# LIDO-HW_100_InputStage_1.net
KiCad netlist of a schematic drawn in Altium Designer
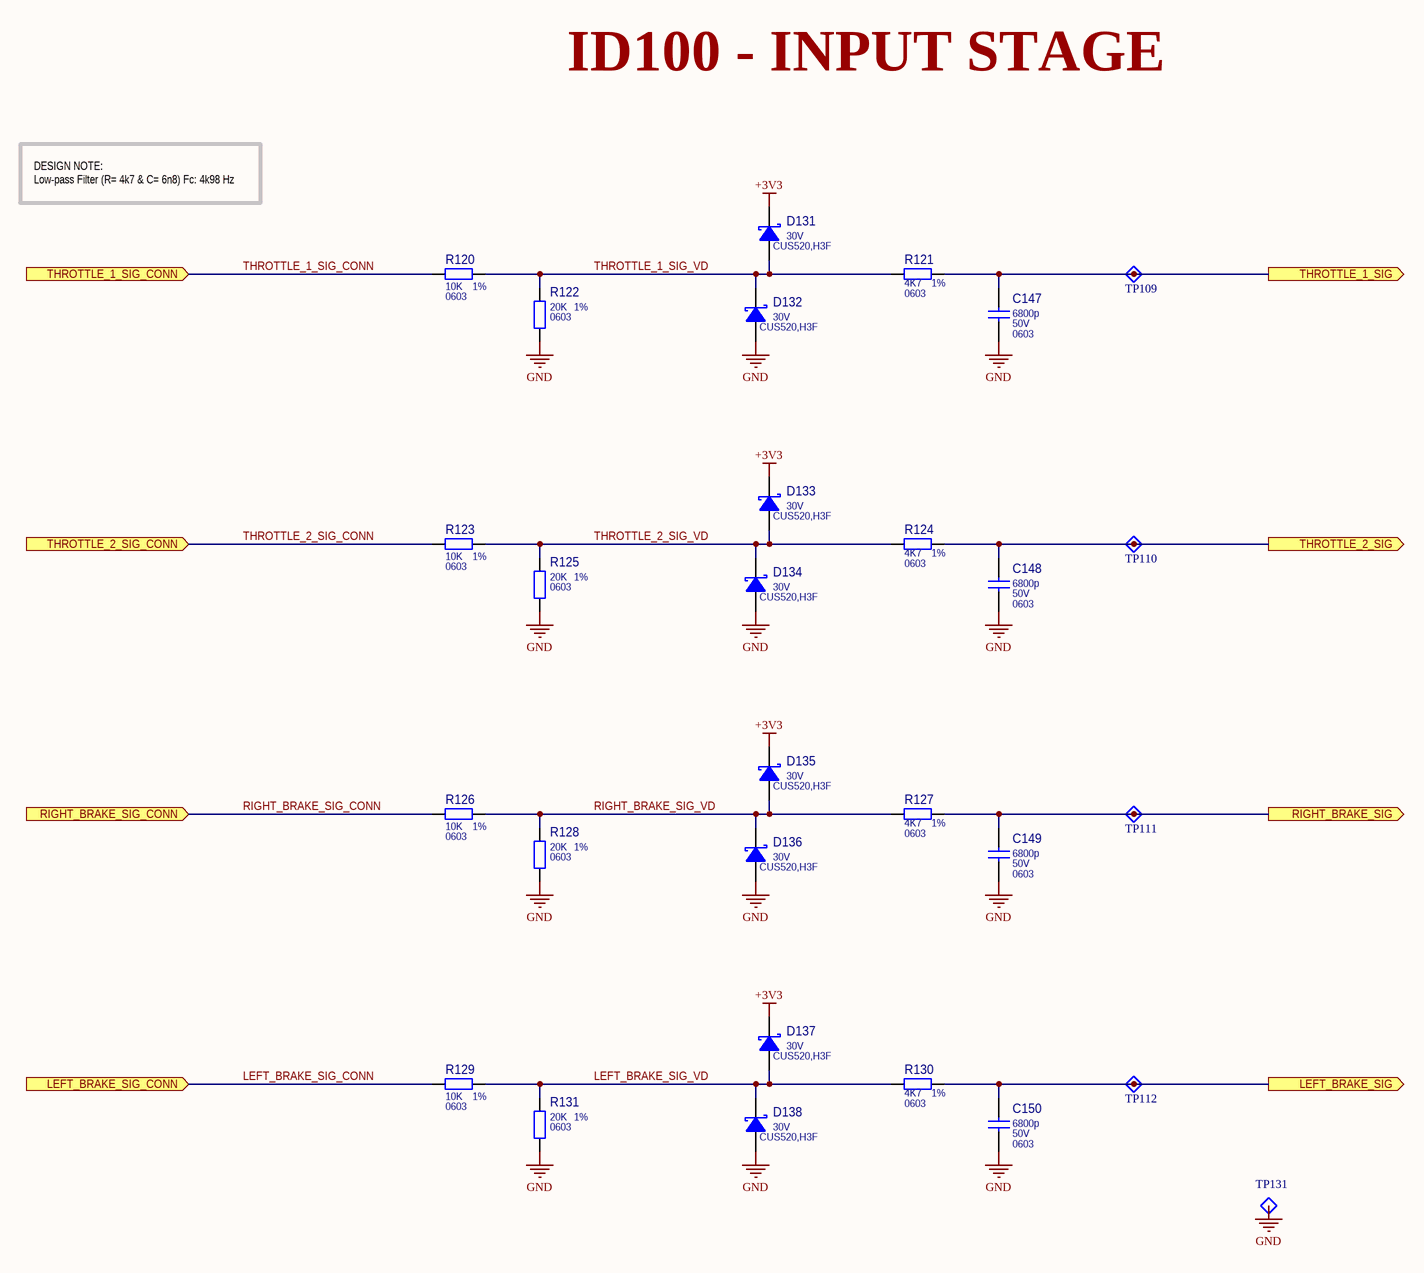
[diagram p0: LIDO-HW.100.InputStage_1.SchDoc]

(export (version "E")
  (design (tool "Eeschema 10.0.6"))
  (components
    (comp (ref "C147")
      (value "6800p")
      (footprint "CAP_0603_1608X90-N_MURATA_A")
      (description "CAP CER 6800PF 50V X7R 0603")
      (fields
        (field (name "MANUFACTURER PART NUMBER") "CGA3E2X7R1H682K080AA")
        (field (name "MANUFACTURER") "TDK Corporation")
        (field (name "PART VALUE 2") "50V")
        (field (name "PART PACKAGE") "0603")
      )
      (libsource (lib "DB_Library") (part "Ceramic"))
    )
    (comp (ref "C148")
      (value "6800p")
      (footprint "CAP_0603_1608X90-N_MURATA_A")
      (description "CAP CER 6800PF 50V X7R 0603")
      (fields
        (field (name "MANUFACTURER PART NUMBER") "CGA3E2X7R1H682K080AA")
        (field (name "MANUFACTURER") "TDK Corporation")
        (field (name "PART VALUE 2") "50V")
        (field (name "PART PACKAGE") "0603")
      )
      (libsource (lib "DB_Library") (part "Ceramic"))
    )
    (comp (ref "C149")
      (value "6800p")
      (footprint "CAP_0603_1608X90-N_MURATA_A")
      (description "CAP CER 6800PF 50V X7R 0603")
      (fields
        (field (name "MANUFACTURER PART NUMBER") "CGA3E2X7R1H682K080AA")
        (field (name "MANUFACTURER") "TDK Corporation")
        (field (name "PART VALUE 2") "50V")
        (field (name "PART PACKAGE") "0603")
      )
      (libsource (lib "DB_Library") (part "Ceramic"))
    )
    (comp (ref "C150")
      (value "6800p")
      (footprint "CAP_0603_1608X90-N_MURATA_A")
      (description "CAP CER 6800PF 50V X7R 0603")
      (fields
        (field (name "MANUFACTURER PART NUMBER") "CGA3E2X7R1H682K080AA")
        (field (name "MANUFACTURER") "TDK Corporation")
        (field (name "PART VALUE 2") "50V")
        (field (name "PART PACKAGE") "0603")
      )
      (libsource (lib "DB_Library") (part "Ceramic"))
    )
    (comp (ref "D131")
      (value "30V")
      (footprint "NXP_SOD-323_250X125X95L30x32_A")
      (description "DIODE SCHOTTKY 30V 200MA")
      (fields
        (field (name "MANUFACTURER PART NUMBER") "CUS520,H3F")
        (field (name "MANUFACTURER") "Toshiba Semiconductor and Storage")
        (field (name "OBSOLETE PART") "False")
      )
      (libsource (lib "DB_Library") (part "Schottky_A"))
    )
    (comp (ref "D132")
      (value "30V")
      (footprint "NXP_SOD-323_250X125X95L30x32_A")
      (description "DIODE SCHOTTKY 30V 200MA")
      (fields
        (field (name "MANUFACTURER PART NUMBER") "CUS520,H3F")
        (field (name "MANUFACTURER") "Toshiba Semiconductor and Storage")
        (field (name "OBSOLETE PART") "False")
      )
      (libsource (lib "DB_Library") (part "Schottky_A"))
    )
    (comp (ref "D133")
      (value "30V")
      (footprint "NXP_SOD-323_250X125X95L30x32_A")
      (description "DIODE SCHOTTKY 30V 200MA")
      (fields
        (field (name "MANUFACTURER PART NUMBER") "CUS520,H3F")
        (field (name "MANUFACTURER") "Toshiba Semiconductor and Storage")
        (field (name "OBSOLETE PART") "False")
      )
      (libsource (lib "DB_Library") (part "Schottky_A"))
    )
    (comp (ref "D134")
      (value "30V")
      (footprint "NXP_SOD-323_250X125X95L30x32_A")
      (description "DIODE SCHOTTKY 30V 200MA")
      (fields
        (field (name "MANUFACTURER PART NUMBER") "CUS520,H3F")
        (field (name "MANUFACTURER") "Toshiba Semiconductor and Storage")
        (field (name "OBSOLETE PART") "False")
      )
      (libsource (lib "DB_Library") (part "Schottky_A"))
    )
    (comp (ref "D135")
      (value "30V")
      (footprint "NXP_SOD-323_250X125X95L30x32_A")
      (description "DIODE SCHOTTKY 30V 200MA")
      (fields
        (field (name "MANUFACTURER PART NUMBER") "CUS520,H3F")
        (field (name "MANUFACTURER") "Toshiba Semiconductor and Storage")
        (field (name "OBSOLETE PART") "False")
      )
      (libsource (lib "DB_Library") (part "Schottky_A"))
    )
    (comp (ref "D136")
      (value "30V")
      (footprint "NXP_SOD-323_250X125X95L30x32_A")
      (description "DIODE SCHOTTKY 30V 200MA")
      (fields
        (field (name "MANUFACTURER PART NUMBER") "CUS520,H3F")
        (field (name "MANUFACTURER") "Toshiba Semiconductor and Storage")
        (field (name "OBSOLETE PART") "False")
      )
      (libsource (lib "DB_Library") (part "Schottky_A"))
    )
    (comp (ref "D137")
      (value "30V")
      (footprint "NXP_SOD-323_250X125X95L30x32_A")
      (description "DIODE SCHOTTKY 30V 200MA")
      (fields
        (field (name "MANUFACTURER PART NUMBER") "CUS520,H3F")
        (field (name "MANUFACTURER") "Toshiba Semiconductor and Storage")
        (field (name "OBSOLETE PART") "False")
      )
      (libsource (lib "DB_Library") (part "Schottky_A"))
    )
    (comp (ref "D138")
      (value "30V")
      (footprint "NXP_SOD-323_250X125X95L30x32_A")
      (description "DIODE SCHOTTKY 30V 200MA")
      (fields
        (field (name "MANUFACTURER PART NUMBER") "CUS520,H3F")
        (field (name "MANUFACTURER") "Toshiba Semiconductor and Storage")
        (field (name "OBSOLETE PART") "False")
      )
      (libsource (lib "DB_Library") (part "Schottky_A"))
    )
    (comp (ref "R120")
      (value "10K")
      (footprint "RES_0603_1608X60-N_YAGEO_A")
      (description "RES 10K OHM 1% 1/10W 0603")
      (fields
        (field (name "MANUFACTURER PART NUMBER") "RC0603FR-0710KL")
        (field (name "MANUFACTURER") "YAGEO")
        (field (name "PART VALUE 2") "1%")
        (field (name "PART PACKAGE") "0603")
      )
      (libsource (lib "DB_Library") (part "Resistor"))
    )
    (comp (ref "R121")
      (value "4K7")
      (footprint "RES_0603_1608X60-N_YAGEO_A")
      (description "RES SMD 4.7K OHM 1% 1/10W 0603")
      (fields
        (field (name "MANUFACTURER PART NUMBER") "ERJ-3EKF4701V")
        (field (name "MANUFACTURER") "Panasonic Electronic Components")
        (field (name "PART VALUE 2") "1%")
        (field (name "PART PACKAGE") "0603")
      )
      (libsource (lib "") (part "Resistor_1"))
    )
    (comp (ref "R122")
      (value "20K")
      (footprint "RES_0603_1608X60-N_YAGEO_A")
      (description "RES SMD 20K OHM 1% 1/10W 0603")
      (fields
        (field (name "MANUFACTURER PART NUMBER") "ERJ-3EKF2002V")
        (field (name "MANUFACTURER") "Panasonic Electronic Components")
        (field (name "PART VALUE 2") "1%")
        (field (name "PART PACKAGE") "0603")
      )
      (libsource (lib "") (part "Resistor_2"))
    )
    (comp (ref "R123")
      (value "10K")
      (footprint "RES_0603_1608X60-N_YAGEO_A")
      (description "RES 10K OHM 1% 1/10W 0603")
      (fields
        (field (name "MANUFACTURER PART NUMBER") "RC0603FR-0710KL")
        (field (name "MANUFACTURER") "YAGEO")
        (field (name "PART VALUE 2") "1%")
        (field (name "PART PACKAGE") "0603")
      )
      (libsource (lib "DB_Library") (part "Resistor"))
    )
    (comp (ref "R124")
      (value "4K7")
      (footprint "RES_0603_1608X60-N_YAGEO_A")
      (description "RES SMD 4.7K OHM 1% 1/10W 0603")
      (fields
        (field (name "MANUFACTURER PART NUMBER") "ERJ-3EKF4701V")
        (field (name "MANUFACTURER") "Panasonic Electronic Components")
        (field (name "PART VALUE 2") "1%")
        (field (name "PART PACKAGE") "0603")
      )
      (libsource (lib "") (part "Resistor_1"))
    )
    (comp (ref "R125")
      (value "20K")
      (footprint "RES_0603_1608X60-N_YAGEO_A")
      (description "RES SMD 20K OHM 1% 1/10W 0603")
      (fields
        (field (name "MANUFACTURER PART NUMBER") "ERJ-3EKF2002V")
        (field (name "MANUFACTURER") "Panasonic Electronic Components")
        (field (name "PART VALUE 2") "1%")
        (field (name "PART PACKAGE") "0603")
      )
      (libsource (lib "") (part "Resistor_2"))
    )
    (comp (ref "R126")
      (value "10K")
      (footprint "RES_0603_1608X60-N_YAGEO_A")
      (description "RES 10K OHM 1% 1/10W 0603")
      (fields
        (field (name "MANUFACTURER PART NUMBER") "RC0603FR-0710KL")
        (field (name "MANUFACTURER") "YAGEO")
        (field (name "PART VALUE 2") "1%")
        (field (name "PART PACKAGE") "0603")
      )
      (libsource (lib "DB_Library") (part "Resistor"))
    )
    (comp (ref "R127")
      (value "4K7")
      (footprint "RES_0603_1608X60-N_YAGEO_A")
      (description "RES SMD 4.7K OHM 1% 1/10W 0603")
      (fields
        (field (name "MANUFACTURER PART NUMBER") "ERJ-3EKF4701V")
        (field (name "MANUFACTURER") "Panasonic Electronic Components")
        (field (name "PART VALUE 2") "1%")
        (field (name "PART PACKAGE") "0603")
      )
      (libsource (lib "") (part "Resistor_1"))
    )
    (comp (ref "R128")
      (value "20K")
      (footprint "RES_0603_1608X60-N_YAGEO_A")
      (description "RES SMD 20K OHM 1% 1/10W 0603")
      (fields
        (field (name "MANUFACTURER PART NUMBER") "ERJ-3EKF2002V")
        (field (name "MANUFACTURER") "Panasonic Electronic Components")
        (field (name "PART VALUE 2") "1%")
        (field (name "PART PACKAGE") "0603")
      )
      (libsource (lib "") (part "Resistor_2"))
    )
    (comp (ref "R129")
      (value "10K")
      (footprint "RES_0603_1608X60-N_YAGEO_A")
      (description "RES 10K OHM 1% 1/10W 0603")
      (fields
        (field (name "MANUFACTURER PART NUMBER") "RC0603FR-0710KL")
        (field (name "MANUFACTURER") "YAGEO")
        (field (name "PART VALUE 2") "1%")
        (field (name "PART PACKAGE") "0603")
      )
      (libsource (lib "DB_Library") (part "Resistor"))
    )
    (comp (ref "R130")
      (value "4K7")
      (footprint "RES_0603_1608X60-N_YAGEO_A")
      (description "RES SMD 4.7K OHM 1% 1/10W 0603")
      (fields
        (field (name "MANUFACTURER PART NUMBER") "ERJ-3EKF4701V")
        (field (name "MANUFACTURER") "Panasonic Electronic Components")
        (field (name "PART VALUE 2") "1%")
        (field (name "PART PACKAGE") "0603")
      )
      (libsource (lib "") (part "Resistor_1"))
    )
    (comp (ref "R131")
      (value "20K")
      (footprint "RES_0603_1608X60-N_YAGEO_A")
      (description "RES SMD 20K OHM 1% 1/10W 0603")
      (fields
        (field (name "MANUFACTURER PART NUMBER") "ERJ-3EKF2002V")
        (field (name "MANUFACTURER") "Panasonic Electronic Components")
        (field (name "PART VALUE 2") "1%")
        (field (name "PART PACKAGE") "0603")
      )
      (libsource (lib "") (part "Resistor_2"))
    )
    (comp (ref "TP109")
      (value "TestPoint_A")
      (footprint "TESTPOINT_1D_A")
      (description "Pad Diamater 1mm")
      (fields (field (name "PART") "Test Point 1D A") (field (name "OBSOLETE PART") "False"))
      (libsource (lib "DB_Library") (part "TestPoint_A"))
    )
    (comp (ref "TP110")
      (value "TestPoint_A")
      (footprint "TESTPOINT_1D_A")
      (description "Pad Diamater 1mm")
      (fields (field (name "PART") "Test Point 1D A") (field (name "OBSOLETE PART") "False"))
      (libsource (lib "DB_Library") (part "TestPoint_A"))
    )
    (comp (ref "TP111")
      (value "TestPoint_A")
      (footprint "TESTPOINT_1D_A")
      (description "Pad Diamater 1mm")
      (fields (field (name "PART") "Test Point 1D A") (field (name "OBSOLETE PART") "False"))
      (libsource (lib "DB_Library") (part "TestPoint_A"))
    )
    (comp (ref "TP112")
      (value "TestPoint_A")
      (footprint "TESTPOINT_1D_A")
      (description "Pad Diamater 1mm")
      (fields (field (name "PART") "Test Point 1D A") (field (name "OBSOLETE PART") "False"))
      (libsource (lib "DB_Library") (part "TestPoint_A"))
    )
    (comp (ref "TP131")
      (value "TestPoint_A")
      (footprint "TESTPOINT_1D_A")
      (description "Pad Diamater 1mm")
      (fields (field (name "PART") "Test Point 1D A") (field (name "OBSOLETE PART") "False"))
      (libsource (lib "DB_Library") (part "TestPoint_A"))
    )
  )
  (nets
    (net (code "1") (name "+3V3") (class "Default")
      (node (ref "D131") (pin "C") (pinfunction "C_C") (pintype "passive"))
      (node (ref "D133") (pin "C") (pinfunction "C_C") (pintype "passive"))
      (node (ref "D135") (pin "C") (pinfunction "C_C") (pintype "passive"))
      (node (ref "D137") (pin "C") (pinfunction "C_C") (pintype "passive"))
    )
    (net (code "2") (name "/LEFT_BRAKE_SIG") (class "Default")
      (node (ref "C150") (pin "1") (pinfunction "1_1") (pintype "passive"))
      (node (ref "R130") (pin "2") (pinfunction "2_2") (pintype "passive"))
      (node (ref "TP112") (pin "1") (pinfunction "TP_1") (pintype "passive"))
    )
    (net (code "3") (name "/LEFT_BRAKE_SIG_CONN") (class "Default")
      (node (ref "R129") (pin "2") (pinfunction "2_2") (pintype "passive"))
    )
    (net (code "4") (name "/LEFT_BRAKE_SIG_VD") (class "Default")
      (node (ref "D137") (pin "A") (pinfunction "A_A") (pintype "passive"))
      (node (ref "D138") (pin "C") (pinfunction "C_C") (pintype "passive"))
      (node (ref "R129") (pin "1") (pinfunction "1_1") (pintype "passive"))
      (node (ref "R130") (pin "1") (pinfunction "1_1") (pintype "passive"))
      (node (ref "R131") (pin "2") (pinfunction "2_2") (pintype "passive"))
    )
    (net (code "5") (name "/RIGHT_BRAKE_SIG") (class "Default")
      (node (ref "C149") (pin "1") (pinfunction "1_1") (pintype "passive"))
      (node (ref "R127") (pin "2") (pinfunction "2_2") (pintype "passive"))
      (node (ref "TP111") (pin "1") (pinfunction "TP_1") (pintype "passive"))
    )
    (net (code "6") (name "/RIGHT_BRAKE_SIG_CONN") (class "Default")
      (node (ref "R126") (pin "2") (pinfunction "2_2") (pintype "passive"))
    )
    (net (code "7") (name "/RIGHT_BRAKE_SIG_VD") (class "Default")
      (node (ref "D135") (pin "A") (pinfunction "A_A") (pintype "passive"))
      (node (ref "D136") (pin "C") (pinfunction "C_C") (pintype "passive"))
      (node (ref "R126") (pin "1") (pinfunction "1_1") (pintype "passive"))
      (node (ref "R127") (pin "1") (pinfunction "1_1") (pintype "passive"))
      (node (ref "R128") (pin "2") (pinfunction "2_2") (pintype "passive"))
    )
    (net (code "8") (name "/THROTTLE_1_SIG") (class "Default")
      (node (ref "C147") (pin "1") (pinfunction "1_1") (pintype "passive"))
      (node (ref "R121") (pin "2") (pinfunction "2_2") (pintype "passive"))
      (node (ref "TP109") (pin "1") (pinfunction "TP_1") (pintype "passive"))
    )
    (net (code "9") (name "/THROTTLE_1_SIG_CONN") (class "Default")
      (node (ref "R120") (pin "2") (pinfunction "2_2") (pintype "passive"))
    )
    (net (code "10") (name "/THROTTLE_1_SIG_VD") (class "Default")
      (node (ref "D131") (pin "A") (pinfunction "A_A") (pintype "passive"))
      (node (ref "D132") (pin "C") (pinfunction "C_C") (pintype "passive"))
      (node (ref "R120") (pin "1") (pinfunction "1_1") (pintype "passive"))
      (node (ref "R121") (pin "1") (pinfunction "1_1") (pintype "passive"))
      (node (ref "R122") (pin "2") (pinfunction "2_2") (pintype "passive"))
    )
    (net (code "11") (name "/THROTTLE_2_SIG") (class "Default")
      (node (ref "C148") (pin "1") (pinfunction "1_1") (pintype "passive"))
      (node (ref "R124") (pin "2") (pinfunction "2_2") (pintype "passive"))
      (node (ref "TP110") (pin "1") (pinfunction "TP_1") (pintype "passive"))
    )
    (net (code "12") (name "/THROTTLE_2_SIG_CONN") (class "Default")
      (node (ref "R123") (pin "2") (pinfunction "2_2") (pintype "passive"))
    )
    (net (code "13") (name "/THROTTLE_2_SIG_VD") (class "Default")
      (node (ref "D133") (pin "A") (pinfunction "A_A") (pintype "passive"))
      (node (ref "D134") (pin "C") (pinfunction "C_C") (pintype "passive"))
      (node (ref "R123") (pin "1") (pinfunction "1_1") (pintype "passive"))
      (node (ref "R124") (pin "1") (pinfunction "1_1") (pintype "passive"))
      (node (ref "R125") (pin "2") (pinfunction "2_2") (pintype "passive"))
    )
    (net (code "14") (name "GND") (class "Default")
      (node (ref "C147") (pin "2") (pinfunction "2_2") (pintype "passive"))
      (node (ref "C148") (pin "2") (pinfunction "2_2") (pintype "passive"))
      (node (ref "C149") (pin "2") (pinfunction "2_2") (pintype "passive"))
      (node (ref "C150") (pin "2") (pinfunction "2_2") (pintype "passive"))
      (node (ref "D132") (pin "A") (pinfunction "A_A") (pintype "passive"))
      (node (ref "D134") (pin "A") (pinfunction "A_A") (pintype "passive"))
      (node (ref "D136") (pin "A") (pinfunction "A_A") (pintype "passive"))
      (node (ref "D138") (pin "A") (pinfunction "A_A") (pintype "passive"))
      (node (ref "R122") (pin "1") (pinfunction "1_1") (pintype "passive"))
      (node (ref "R125") (pin "1") (pinfunction "1_1") (pintype "passive"))
      (node (ref "R128") (pin "1") (pinfunction "1_1") (pintype "passive"))
      (node (ref "R131") (pin "1") (pinfunction "1_1") (pintype "passive"))
      (node (ref "TP131") (pin "1") (pinfunction "TP_1") (pintype "passive"))
    )
  )
)
